# circuito_v6-pv.net
KiCad netlist of a schematic drawn in EAGLE
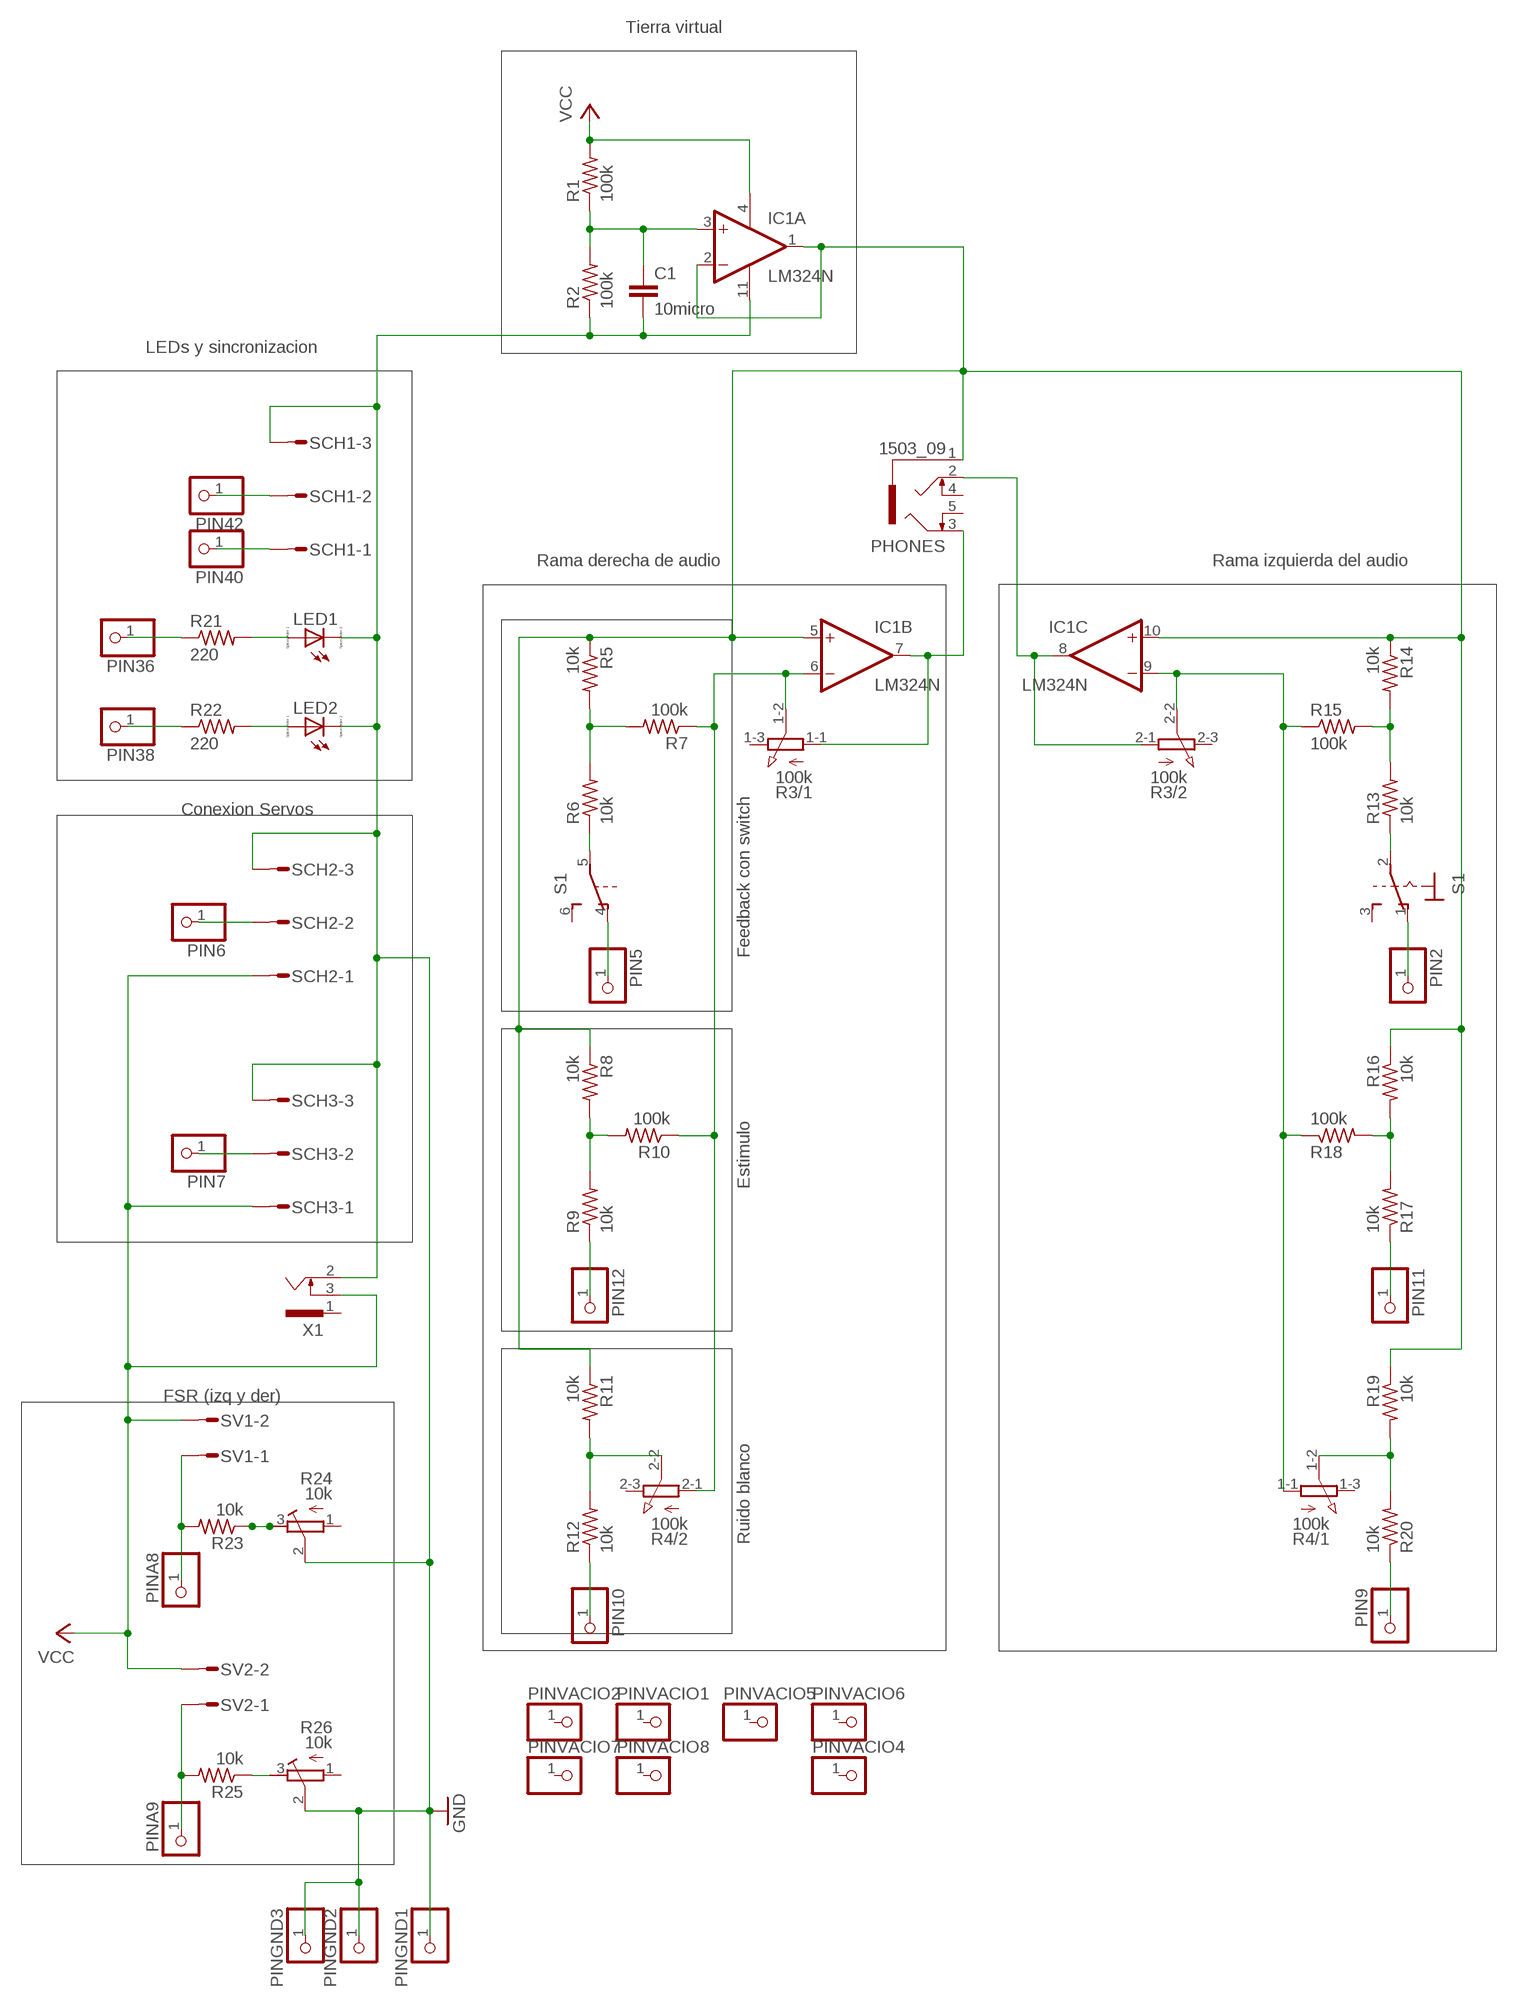
[diagram p0: schematic, sheet 1]

(export (version "E")
  (design (tool "Eeschema 10.0.6"))
  (components
    (comp (ref "C1")
      (value "10micro")
      (footprint "eagle-import:C025-030X050")
      (libsource (lib "eagle-import") (part "C-EU025-030X050"))
    )
    (comp (ref "IC1")
      (value "LM324N")
      (footprint "eagle-import:DIL14")
      (fields (field (name "SPICEPREFIX") "X"))
      (libsource (lib "eagle-import") (part "LM324N"))
    )
    (comp (ref "LED1")
      (value "LED_ELD260")
      (footprint "eagle-import:LED_LD260")
      (fields (field (name "SPICEMODEL") "DMOD"))
      (libsource (lib "eagle-import") (part "LED_ELD260"))
    )
    (comp (ref "LED2")
      (value "LED_ELD260")
      (footprint "eagle-import:LED_LD260")
      (fields (field (name "SPICEMODEL") "DMOD"))
      (libsource (lib "eagle-import") (part "LED_ELD260"))
    )
    (comp (ref "PHONES")
      (value "1503_09")
      (footprint "eagle-import:1503_09")
      (fields (field (name "SPICEPREFIX") "X"))
      (libsource (lib "eagle-import") (part "1503_09"))
    )
    (comp (ref "PIN2")
      (value "PINHD-1X1")
      (footprint "eagle-import:1X01")
      (fields (field (name "SPICEPREFIX") "X"))
      (libsource (lib "eagle-import") (part "PINHD-1X1"))
    )
    (comp (ref "PIN5")
      (value "PINHD-1X1")
      (footprint "eagle-import:1X01")
      (fields (field (name "SPICEPREFIX") "X"))
      (libsource (lib "eagle-import") (part "PINHD-1X1"))
    )
    (comp (ref "PIN6")
      (value "PINHD-1X1")
      (footprint "eagle-import:1X01")
      (fields (field (name "SPICEPREFIX") "X"))
      (libsource (lib "eagle-import") (part "PINHD-1X1"))
    )
    (comp (ref "PIN7")
      (value "PINHD-1X1")
      (footprint "eagle-import:1X01")
      (fields (field (name "SPICEPREFIX") "X"))
      (libsource (lib "eagle-import") (part "PINHD-1X1"))
    )
    (comp (ref "PIN9")
      (value "PINHD-1X1")
      (footprint "eagle-import:1X01")
      (fields (field (name "SPICEPREFIX") "X"))
      (libsource (lib "eagle-import") (part "PINHD-1X1"))
    )
    (comp (ref "PIN10")
      (value "PINHD-1X1")
      (footprint "eagle-import:1X01")
      (fields (field (name "SPICEPREFIX") "X"))
      (libsource (lib "eagle-import") (part "PINHD-1X1"))
    )
    (comp (ref "PIN11")
      (value "PINHD-1X1")
      (footprint "eagle-import:1X01")
      (fields (field (name "SPICEPREFIX") "X"))
      (libsource (lib "eagle-import") (part "PINHD-1X1"))
    )
    (comp (ref "PIN12")
      (value "PINHD-1X1")
      (footprint "eagle-import:1X01")
      (fields (field (name "SPICEPREFIX") "X"))
      (libsource (lib "eagle-import") (part "PINHD-1X1"))
    )
    (comp (ref "PIN36")
      (value "PINHD-1X1")
      (footprint "eagle-import:1X01")
      (fields (field (name "SPICEPREFIX") "X"))
      (libsource (lib "eagle-import") (part "PINHD-1X1"))
    )
    (comp (ref "PIN38")
      (value "PINHD-1X1")
      (footprint "eagle-import:1X01")
      (fields (field (name "SPICEPREFIX") "X"))
      (libsource (lib "eagle-import") (part "PINHD-1X1"))
    )
    (comp (ref "PIN40")
      (value "PINHD-1X1")
      (footprint "eagle-import:1X01")
      (fields (field (name "SPICEPREFIX") "X"))
      (libsource (lib "eagle-import") (part "PINHD-1X1"))
    )
    (comp (ref "PIN42")
      (value "PINHD-1X1")
      (footprint "eagle-import:1X01")
      (fields (field (name "SPICEPREFIX") "X"))
      (libsource (lib "eagle-import") (part "PINHD-1X1"))
    )
    (comp (ref "PINA8")
      (value "PINHD-1X1")
      (footprint "eagle-import:1X01")
      (fields (field (name "SPICEPREFIX") "X"))
      (libsource (lib "eagle-import") (part "PINHD-1X1"))
    )
    (comp (ref "PINA9")
      (value "PINHD-1X1")
      (footprint "eagle-import:1X01")
      (fields (field (name "SPICEPREFIX") "X"))
      (libsource (lib "eagle-import") (part "PINHD-1X1"))
    )
    (comp (ref "PINGND1")
      (value "PINHD-1X1")
      (footprint "eagle-import:1X01")
      (fields (field (name "SPICEPREFIX") "X"))
      (libsource (lib "eagle-import") (part "PINHD-1X1"))
    )
    (comp (ref "PINGND2")
      (value "PINHD-1X1")
      (footprint "eagle-import:1X01")
      (fields (field (name "SPICEPREFIX") "X"))
      (libsource (lib "eagle-import") (part "PINHD-1X1"))
    )
    (comp (ref "PINGND3")
      (value "PINHD-1X1")
      (footprint "eagle-import:1X01")
      (fields (field (name "SPICEPREFIX") "X"))
      (libsource (lib "eagle-import") (part "PINHD-1X1"))
    )
    (comp (ref "PINVACIO1")
      (value "PINHD-1X1")
      (footprint "eagle-import:1X01")
      (fields (field (name "SPICEPREFIX") "X"))
      (libsource (lib "eagle-import") (part "PINHD-1X1"))
    )
    (comp (ref "PINVACIO2")
      (value "PINHD-1X1")
      (footprint "eagle-import:1X01")
      (fields (field (name "SPICEPREFIX") "X"))
      (libsource (lib "eagle-import") (part "PINHD-1X1"))
    )
    (comp (ref "PINVACIO4")
      (value "PINHD-1X1")
      (footprint "eagle-import:1X01")
      (fields (field (name "SPICEPREFIX") "X"))
      (libsource (lib "eagle-import") (part "PINHD-1X1"))
    )
    (comp (ref "PINVACIO5")
      (value "PINHD-1X1")
      (footprint "eagle-import:1X01")
      (fields (field (name "SPICEPREFIX") "X"))
      (libsource (lib "eagle-import") (part "PINHD-1X1"))
    )
    (comp (ref "PINVACIO6")
      (value "PINHD-1X1")
      (footprint "eagle-import:1X01")
      (fields (field (name "SPICEPREFIX") "X"))
      (libsource (lib "eagle-import") (part "PINHD-1X1"))
    )
    (comp (ref "PINVACIO7")
      (value "PINHD-1X1")
      (footprint "eagle-import:1X01")
      (fields (field (name "SPICEPREFIX") "X"))
      (libsource (lib "eagle-import") (part "PINHD-1X1"))
    )
    (comp (ref "PINVACIO8")
      (value "PINHD-1X1")
      (footprint "eagle-import:1X01")
      (fields (field (name "SPICEPREFIX") "X"))
      (libsource (lib "eagle-import") (part "PINHD-1X1"))
    )
    (comp (ref "R1")
      (value "100k")
      (footprint "eagle-import:0207_7")
      (libsource (lib "eagle-import") (part "R-US_0207/7"))
    )
    (comp (ref "R2")
      (value "100k")
      (footprint "eagle-import:0207_7")
      (libsource (lib "eagle-import") (part "R-US_0207/7"))
    )
    (comp (ref "R3")
      (value "100k")
      (footprint "eagle-import:3RP_1610G")
      (fields (field (name "SPICEPREFIX") "J"))
      (libsource (lib "eagle-import") (part "3RP/1610G"))
    )
    (comp (ref "R4")
      (value "100k")
      (footprint "eagle-import:3RP_1610G")
      (fields (field (name "SPICEPREFIX") "J"))
      (libsource (lib "eagle-import") (part "3RP/1610G"))
    )
    (comp (ref "R5")
      (value "10k")
      (footprint "eagle-import:0207_7")
      (libsource (lib "eagle-import") (part "R-US_0207/7"))
    )
    (comp (ref "R6")
      (value "10k")
      (footprint "eagle-import:0207_7")
      (libsource (lib "eagle-import") (part "R-US_0207/7"))
    )
    (comp (ref "R7")
      (value "100k")
      (footprint "eagle-import:0207_7")
      (libsource (lib "eagle-import") (part "R-US_0207/7"))
    )
    (comp (ref "R8")
      (value "10k")
      (footprint "eagle-import:0207_7")
      (libsource (lib "eagle-import") (part "R-US_0207/7"))
    )
    (comp (ref "R9")
      (value "10k")
      (footprint "eagle-import:0207_7")
      (libsource (lib "eagle-import") (part "R-US_0207/7"))
    )
    (comp (ref "R10")
      (value "100k")
      (footprint "eagle-import:0207_7")
      (libsource (lib "eagle-import") (part "R-US_0207/7"))
    )
    (comp (ref "R11")
      (value "10k")
      (footprint "eagle-import:0207_7")
      (libsource (lib "eagle-import") (part "R-US_0207/7"))
    )
    (comp (ref "R12")
      (value "10k")
      (footprint "eagle-import:0207_7")
      (libsource (lib "eagle-import") (part "R-US_0207/7"))
    )
    (comp (ref "R13")
      (value "10k")
      (footprint "eagle-import:0207_7")
      (libsource (lib "eagle-import") (part "R-US_0207/7"))
    )
    (comp (ref "R14")
      (value "10k")
      (footprint "eagle-import:0207_7")
      (libsource (lib "eagle-import") (part "R-US_0207/7"))
    )
    (comp (ref "R15")
      (value "100k")
      (footprint "eagle-import:0207_7")
      (libsource (lib "eagle-import") (part "R-US_0207/7"))
    )
    (comp (ref "R16")
      (value "10k")
      (footprint "eagle-import:0207_7")
      (libsource (lib "eagle-import") (part "R-US_0207/7"))
    )
    (comp (ref "R17")
      (value "10k")
      (footprint "eagle-import:0207_7")
      (libsource (lib "eagle-import") (part "R-US_0207/7"))
    )
    (comp (ref "R18")
      (value "100k")
      (footprint "eagle-import:0207_7")
      (libsource (lib "eagle-import") (part "R-US_0207/7"))
    )
    (comp (ref "R19")
      (value "10k")
      (footprint "eagle-import:0207_7")
      (libsource (lib "eagle-import") (part "R-US_0207/7"))
    )
    (comp (ref "R20")
      (value "10k")
      (footprint "eagle-import:0207_7")
      (libsource (lib "eagle-import") (part "R-US_0207/7"))
    )
    (comp (ref "R21")
      (value "220")
      (footprint "eagle-import:0207_7")
      (libsource (lib "eagle-import") (part "R-US_0207/7"))
    )
    (comp (ref "R22")
      (value "220")
      (footprint "eagle-import:0207_7")
      (libsource (lib "eagle-import") (part "R-US_0207/7"))
    )
    (comp (ref "R23")
      (value "10k")
      (footprint "eagle-import:0207_7")
      (libsource (lib "eagle-import") (part "R-US_0207/7"))
    )
    (comp (ref "R24")
      (value "10k")
      (footprint "eagle-import:RTRIM64W")
      (libsource (lib "eagle-import") (part "R-TRIMM64W"))
    )
    (comp (ref "R25")
      (value "10k")
      (footprint "eagle-import:0207_7")
      (libsource (lib "eagle-import") (part "R-US_0207/7"))
    )
    (comp (ref "R26")
      (value "10k")
      (footprint "eagle-import:RTRIM64W")
      (libsource (lib "eagle-import") (part "R-TRIMM64W"))
    )
    (comp (ref "S1")
      (value "320-938")
      (footprint "eagle-import:320-938")
      (libsource (lib "eagle-import") (part "320-938"))
    )
    (comp (ref "SCH1")
      (value "L03P")
      (footprint "eagle-import:L03P")
      (fields (field (name "SPICEPREFIX") "X"))
      (libsource (lib "eagle-import") (part "L03P"))
    )
    (comp (ref "SCH2")
      (value "L03P")
      (footprint "eagle-import:L03P")
      (fields (field (name "SPICEPREFIX") "X"))
      (libsource (lib "eagle-import") (part "L03P"))
    )
    (comp (ref "SCH3")
      (value "L03P")
      (footprint "eagle-import:L03P")
      (fields (field (name "SPICEPREFIX") "X"))
      (libsource (lib "eagle-import") (part "L03P"))
    )
    (comp (ref "SV1")
      (value "L02P")
      (footprint "eagle-import:L02P")
      (fields (field (name "SPICEPREFIX") "X"))
      (libsource (lib "eagle-import") (part "L02P"))
    )
    (comp (ref "SV2")
      (value "L02P")
      (footprint "eagle-import:L02P")
      (fields (field (name "SPICEPREFIX") "X"))
      (libsource (lib "eagle-import") (part "L02P"))
    )
    (comp (ref "X1")
      (value "SCD-014A")
      (footprint "eagle-import:SCD-014-A")
      (fields (field (name "SPICEPREFIX") "X"))
      (libsource (lib "eagle-import") (part "SCD-014A"))
    )
  )
  (nets
    (net (code "1") (name "GND") (class "Default")
      (node (ref "C1") (pin "2") (pinfunction "2_2") (pintype "passive"))
      (node (ref "IC1") (pin "11") (pinfunction "V-_11") (pintype "power_in"))
      (node (ref "LED1") (pin "K") (pinfunction "C_K") (pintype "passive"))
      (node (ref "LED2") (pin "K") (pinfunction "C_K") (pintype "passive"))
      (node (ref "PINGND1") (pin "1") (pinfunction "1_1") (pintype "passive"))
      (node (ref "PINGND2") (pin "1") (pinfunction "1_1") (pintype "passive"))
      (node (ref "PINGND3") (pin "1") (pinfunction "1_1") (pintype "passive"))
      (node (ref "R2") (pin "1") (pinfunction "1_1") (pintype "passive"))
      (node (ref "R24") (pin "2") (pinfunction "S_2") (pintype "passive"))
      (node (ref "R26") (pin "2") (pinfunction "S_2") (pintype "passive"))
      (node (ref "SCH1") (pin "3") (pinfunction "S_3") (pintype "passive"))
      (node (ref "SCH2") (pin "3") (pinfunction "S_3") (pintype "passive"))
      (node (ref "SCH3") (pin "3") (pinfunction "S_3") (pintype "passive"))
      (node (ref "X1") (pin "2") (pinfunction "2_2") (pintype "passive"))
    )
    (net (code "2") (name "Net-(IC1A-+IN)") (class "Default")
      (node (ref "C1") (pin "1") (pinfunction "1_1") (pintype "passive"))
      (node (ref "IC1") (pin "3") (pinfunction "+IN_3") (pintype "input"))
      (node (ref "R1") (pin "1") (pinfunction "1_1") (pintype "passive"))
      (node (ref "R2") (pin "2") (pinfunction "2_2") (pintype "passive"))
    )
    (net (code "3") (name "Net-(IC1A--IN)") (class "Default")
      (node (ref "IC1") (pin "1") (pinfunction "OUT_1") (pintype "output"))
      (node (ref "IC1") (pin "10") (pinfunction "+IN_10") (pintype "input"))
      (node (ref "IC1") (pin "2") (pinfunction "-IN_2") (pintype "input"))
      (node (ref "IC1") (pin "5") (pinfunction "+IN_5") (pintype "input"))
      (node (ref "PHONES") (pin "1") (pinfunction "1_1") (pintype "passive"))
      (node (ref "R11") (pin "1") (pinfunction "1_1") (pintype "passive"))
      (node (ref "R14") (pin "1") (pinfunction "1_1") (pintype "passive"))
      (node (ref "R16") (pin "1") (pinfunction "1_1") (pintype "passive"))
      (node (ref "R19") (pin "1") (pinfunction "1_1") (pintype "passive"))
      (node (ref "R5") (pin "1") (pinfunction "1_1") (pintype "passive"))
      (node (ref "R8") (pin "1") (pinfunction "1_1") (pintype "passive"))
    )
    (net (code "4") (name "Net-(IC1B--IN)") (class "Default")
      (node (ref "IC1") (pin "6") (pinfunction "-IN_6") (pintype "input"))
      (node (ref "R10") (pin "1") (pinfunction "1_1") (pintype "passive"))
      (node (ref "R3") (pin "1-2") (pinfunction "S_1-2") (pintype "passive"))
      (node (ref "R4") (pin "2-1") (pinfunction "A_2-1") (pintype "passive"))
      (node (ref "R7") (pin "1") (pinfunction "1_1") (pintype "passive"))
    )
    (net (code "5") (name "Net-(IC1B-OUT)") (class "Default")
      (node (ref "IC1") (pin "7") (pinfunction "OUT_7") (pintype "output"))
      (node (ref "PHONES") (pin "3") (pinfunction "3_3") (pintype "passive"))
      (node (ref "R3") (pin "1-1") (pinfunction "A_1-1") (pintype "passive"))
    )
    (net (code "6") (name "Net-(IC1C--IN)") (class "Default")
      (node (ref "IC1") (pin "9") (pinfunction "-IN_9") (pintype "input"))
      (node (ref "R15") (pin "1") (pinfunction "1_1") (pintype "passive"))
      (node (ref "R18") (pin "1") (pinfunction "1_1") (pintype "passive"))
      (node (ref "R3") (pin "2-2") (pinfunction "S_2-2") (pintype "passive"))
      (node (ref "R4") (pin "1-1") (pinfunction "A_1-1") (pintype "passive"))
    )
    (net (code "7") (name "Net-(IC1C-OUT)") (class "Default")
      (node (ref "IC1") (pin "8") (pinfunction "OUT_8") (pintype "output"))
      (node (ref "PHONES") (pin "2") (pinfunction "2_2") (pintype "passive"))
      (node (ref "R3") (pin "2-1") (pinfunction "A_2-1") (pintype "passive"))
    )
    (net (code "8") (name "Net-(LED1-PadA)") (class "Default")
      (node (ref "LED1") (pin "A") (pinfunction "A_A") (pintype "passive"))
      (node (ref "R21") (pin "2") (pinfunction "2_2") (pintype "passive"))
    )
    (net (code "9") (name "Net-(LED2-PadA)") (class "Default")
      (node (ref "LED2") (pin "A") (pinfunction "A_A") (pintype "passive"))
      (node (ref "R22") (pin "2") (pinfunction "2_2") (pintype "passive"))
    )
    (net (code "10") (name "Net-(PIN9-Pad1)") (class "Default")
      (node (ref "PIN9") (pin "1") (pinfunction "1_1") (pintype "passive"))
      (node (ref "R20") (pin "1") (pinfunction "1_1") (pintype "passive"))
    )
    (net (code "11") (name "Net-(PIN10-Pad1)") (class "Default")
      (node (ref "PIN10") (pin "1") (pinfunction "1_1") (pintype "passive"))
      (node (ref "R12") (pin "1") (pinfunction "1_1") (pintype "passive"))
    )
    (net (code "12") (name "Net-(PIN11-Pad1)") (class "Default")
      (node (ref "PIN11") (pin "1") (pinfunction "1_1") (pintype "passive"))
      (node (ref "R17") (pin "1") (pinfunction "1_1") (pintype "passive"))
    )
    (net (code "13") (name "Net-(PIN12-Pad1)") (class "Default")
      (node (ref "PIN12") (pin "1") (pinfunction "1_1") (pintype "passive"))
      (node (ref "R9") (pin "1") (pinfunction "1_1") (pintype "passive"))
    )
    (net (code "14") (name "Net-(PIN36-Pad1)") (class "Default")
      (node (ref "PIN36") (pin "1") (pinfunction "1_1") (pintype "passive"))
      (node (ref "R21") (pin "1") (pinfunction "1_1") (pintype "passive"))
    )
    (net (code "15") (name "Net-(PIN38-Pad1)") (class "Default")
      (node (ref "PIN38") (pin "1") (pinfunction "1_1") (pintype "passive"))
      (node (ref "R22") (pin "1") (pinfunction "1_1") (pintype "passive"))
    )
    (net (code "16") (name "Net-(R4A-S)") (class "Default")
      (node (ref "R19") (pin "2") (pinfunction "2_2") (pintype "passive"))
      (node (ref "R20") (pin "2") (pinfunction "2_2") (pintype "passive"))
      (node (ref "R4") (pin "1-2") (pinfunction "S_1-2") (pintype "passive"))
    )
    (net (code "17") (name "Net-(R4B-S)") (class "Default")
      (node (ref "R11") (pin "2") (pinfunction "2_2") (pintype "passive"))
      (node (ref "R12") (pin "2") (pinfunction "2_2") (pintype "passive"))
      (node (ref "R4") (pin "2-2") (pinfunction "S_2-2") (pintype "passive"))
    )
    (net (code "18") (name "Net-(R5-Pad2)") (class "Default")
      (node (ref "R5") (pin "2") (pinfunction "2_2") (pintype "passive"))
      (node (ref "R6") (pin "2") (pinfunction "2_2") (pintype "passive"))
      (node (ref "R7") (pin "2") (pinfunction "2_2") (pintype "passive"))
    )
    (net (code "19") (name "Net-(R10-Pad2)") (class "Default")
      (node (ref "R10") (pin "2") (pinfunction "2_2") (pintype "passive"))
      (node (ref "R8") (pin "2") (pinfunction "2_2") (pintype "passive"))
      (node (ref "R9") (pin "2") (pinfunction "2_2") (pintype "passive"))
    )
    (net (code "20") (name "Net-(R13-Pad2)") (class "Default")
      (node (ref "R13") (pin "2") (pinfunction "2_2") (pintype "passive"))
      (node (ref "R14") (pin "2") (pinfunction "2_2") (pintype "passive"))
      (node (ref "R15") (pin "2") (pinfunction "2_2") (pintype "passive"))
    )
    (net (code "21") (name "Net-(R16-Pad2)") (class "Default")
      (node (ref "R16") (pin "2") (pinfunction "2_2") (pintype "passive"))
      (node (ref "R17") (pin "2") (pinfunction "2_2") (pintype "passive"))
      (node (ref "R18") (pin "2") (pinfunction "2_2") (pintype "passive"))
    )
    (net (code "22") (name "Net-(R24-E)") (class "Default")
      (node (ref "R23") (pin "1") (pinfunction "1_1") (pintype "passive"))
      (node (ref "R24") (pin "3") (pinfunction "E_3") (pintype "passive"))
    )
    (net (code "23") (name "Net-(R26-E)") (class "Default")
      (node (ref "R25") (pin "1") (pinfunction "1_1") (pintype "passive"))
      (node (ref "R26") (pin "3") (pinfunction "E_3") (pintype "passive"))
    )
    (net (code "24") (name "Net-(S1A-O)") (class "Default")
      (node (ref "PIN2") (pin "1") (pinfunction "1_1") (pintype "passive"))
      (node (ref "S1") (pin "1") (pinfunction "O_1") (pintype "passive"))
    )
    (net (code "25") (name "Net-(S1A-P)") (class "Default")
      (node (ref "R13") (pin "1") (pinfunction "1_1") (pintype "passive"))
      (node (ref "S1") (pin "2") (pinfunction "P_2") (pintype "passive"))
    )
    (net (code "26") (name "Net-(S1B-O)") (class "Default")
      (node (ref "PIN5") (pin "1") (pinfunction "1_1") (pintype "passive"))
      (node (ref "S1") (pin "4") (pinfunction "O_4") (pintype "passive"))
    )
    (net (code "27") (name "Net-(S1B-P)") (class "Default")
      (node (ref "R6") (pin "1") (pinfunction "1_1") (pintype "passive"))
      (node (ref "S1") (pin "5") (pinfunction "P_5") (pintype "passive"))
    )
    (net (code "28") (name "Net-(SCH1A-S)") (class "Default")
      (node (ref "PIN40") (pin "1") (pinfunction "1_1") (pintype "passive"))
      (node (ref "SCH1") (pin "1") (pinfunction "S_1") (pintype "passive"))
    )
    (net (code "29") (name "Net-(SCH1B-S)") (class "Default")
      (node (ref "PIN42") (pin "1") (pinfunction "1_1") (pintype "passive"))
      (node (ref "SCH1") (pin "2") (pinfunction "S_2") (pintype "passive"))
    )
    (net (code "30") (name "Net-(SCH2B-S)") (class "Default")
      (node (ref "PIN6") (pin "1") (pinfunction "1_1") (pintype "passive"))
      (node (ref "SCH2") (pin "2") (pinfunction "S_2") (pintype "passive"))
    )
    (net (code "31") (name "Net-(SCH3B-S)") (class "Default")
      (node (ref "PIN7") (pin "1") (pinfunction "1_1") (pintype "passive"))
      (node (ref "SCH3") (pin "2") (pinfunction "S_2") (pintype "passive"))
    )
    (net (code "32") (name "Net-(SV1A-S)") (class "Default")
      (node (ref "PINA8") (pin "1") (pinfunction "1_1") (pintype "passive"))
      (node (ref "R23") (pin "2") (pinfunction "2_2") (pintype "passive"))
      (node (ref "SV1") (pin "1") (pinfunction "S_1") (pintype "passive"))
    )
    (net (code "33") (name "Net-(SV2A-S)") (class "Default")
      (node (ref "PINA9") (pin "1") (pinfunction "1_1") (pintype "passive"))
      (node (ref "R25") (pin "2") (pinfunction "2_2") (pintype "passive"))
      (node (ref "SV2") (pin "1") (pinfunction "S_1") (pintype "passive"))
    )
    (net (code "34") (name "VCC") (class "Default")
      (node (ref "IC1") (pin "4") (pinfunction "V+_4") (pintype "power_in"))
      (node (ref "R1") (pin "2") (pinfunction "2_2") (pintype "passive"))
      (node (ref "SCH2") (pin "1") (pinfunction "S_1") (pintype "passive"))
      (node (ref "SCH3") (pin "1") (pinfunction "S_1") (pintype "passive"))
      (node (ref "SV1") (pin "2") (pinfunction "S_2") (pintype "passive"))
      (node (ref "SV2") (pin "2") (pinfunction "S_2") (pintype "passive"))
      (node (ref "X1") (pin "3") (pinfunction "3_3") (pintype "passive"))
    )
    (net (code "35") (name "unconnected-(PHONES-Pad4)") (class "Default")
      (node (ref "PHONES") (pin "4") (pinfunction "4_4") (pintype "passive"))
    )
    (net (code "36") (name "unconnected-(PHONES-Pad5)") (class "Default")
      (node (ref "PHONES") (pin "5") (pinfunction "5_5") (pintype "passive"))
    )
    (net (code "37") (name "unconnected-(PINVACIO1-Pad1)") (class "Default")
      (node (ref "PINVACIO1") (pin "1") (pinfunction "1_1") (pintype "passive"))
    )
    (net (code "38") (name "unconnected-(PINVACIO2-Pad1)") (class "Default")
      (node (ref "PINVACIO2") (pin "1") (pinfunction "1_1") (pintype "passive"))
    )
    (net (code "39") (name "unconnected-(PINVACIO4-Pad1)") (class "Default")
      (node (ref "PINVACIO4") (pin "1") (pinfunction "1_1") (pintype "passive"))
    )
    (net (code "40") (name "unconnected-(PINVACIO5-Pad1)") (class "Default")
      (node (ref "PINVACIO5") (pin "1") (pinfunction "1_1") (pintype "passive"))
    )
    (net (code "41") (name "unconnected-(PINVACIO6-Pad1)") (class "Default")
      (node (ref "PINVACIO6") (pin "1") (pinfunction "1_1") (pintype "passive"))
    )
    (net (code "42") (name "unconnected-(PINVACIO7-Pad1)") (class "Default")
      (node (ref "PINVACIO7") (pin "1") (pinfunction "1_1") (pintype "passive"))
    )
    (net (code "43") (name "unconnected-(PINVACIO8-Pad1)") (class "Default")
      (node (ref "PINVACIO8") (pin "1") (pinfunction "1_1") (pintype "passive"))
    )
    (net (code "44") (name "unconnected-(R3A-E-Pad1-3)") (class "Default")
      (node (ref "R3") (pin "1-3") (pinfunction "E_1-3") (pintype "passive"))
    )
    (net (code "45") (name "unconnected-(R3B-E-Pad2-3)") (class "Default")
      (node (ref "R3") (pin "2-3") (pinfunction "E_2-3") (pintype "passive"))
    )
    (net (code "46") (name "unconnected-(R4A-E-Pad1-3)") (class "Default")
      (node (ref "R4") (pin "1-3") (pinfunction "E_1-3") (pintype "passive"))
    )
    (net (code "47") (name "unconnected-(R4B-E-Pad2-3)") (class "Default")
      (node (ref "R4") (pin "2-3") (pinfunction "E_2-3") (pintype "passive"))
    )
    (net (code "48") (name "unconnected-(R24-A-Pad1)") (class "Default")
      (node (ref "R24") (pin "1") (pinfunction "A_1") (pintype "passive"))
    )
    (net (code "49") (name "unconnected-(R26-A-Pad1)") (class "Default")
      (node (ref "R26") (pin "1") (pinfunction "A_1") (pintype "passive"))
    )
    (net (code "50") (name "unconnected-(S1A-S-Pad3)") (class "Default")
      (node (ref "S1") (pin "3") (pinfunction "S_3") (pintype "passive"))
    )
    (net (code "51") (name "unconnected-(S1B-S-Pad6)") (class "Default")
      (node (ref "S1") (pin "6") (pinfunction "S_6") (pintype "passive"))
    )
    (net (code "52") (name "unconnected-(X1-Pad1)") (class "Default")
      (node (ref "X1") (pin "1") (pinfunction "1_1") (pintype "passive"))
    )
  )
)
